# 1-Schematic_UA741.net
KiCad netlist of a schematic drawn in EasyEDA
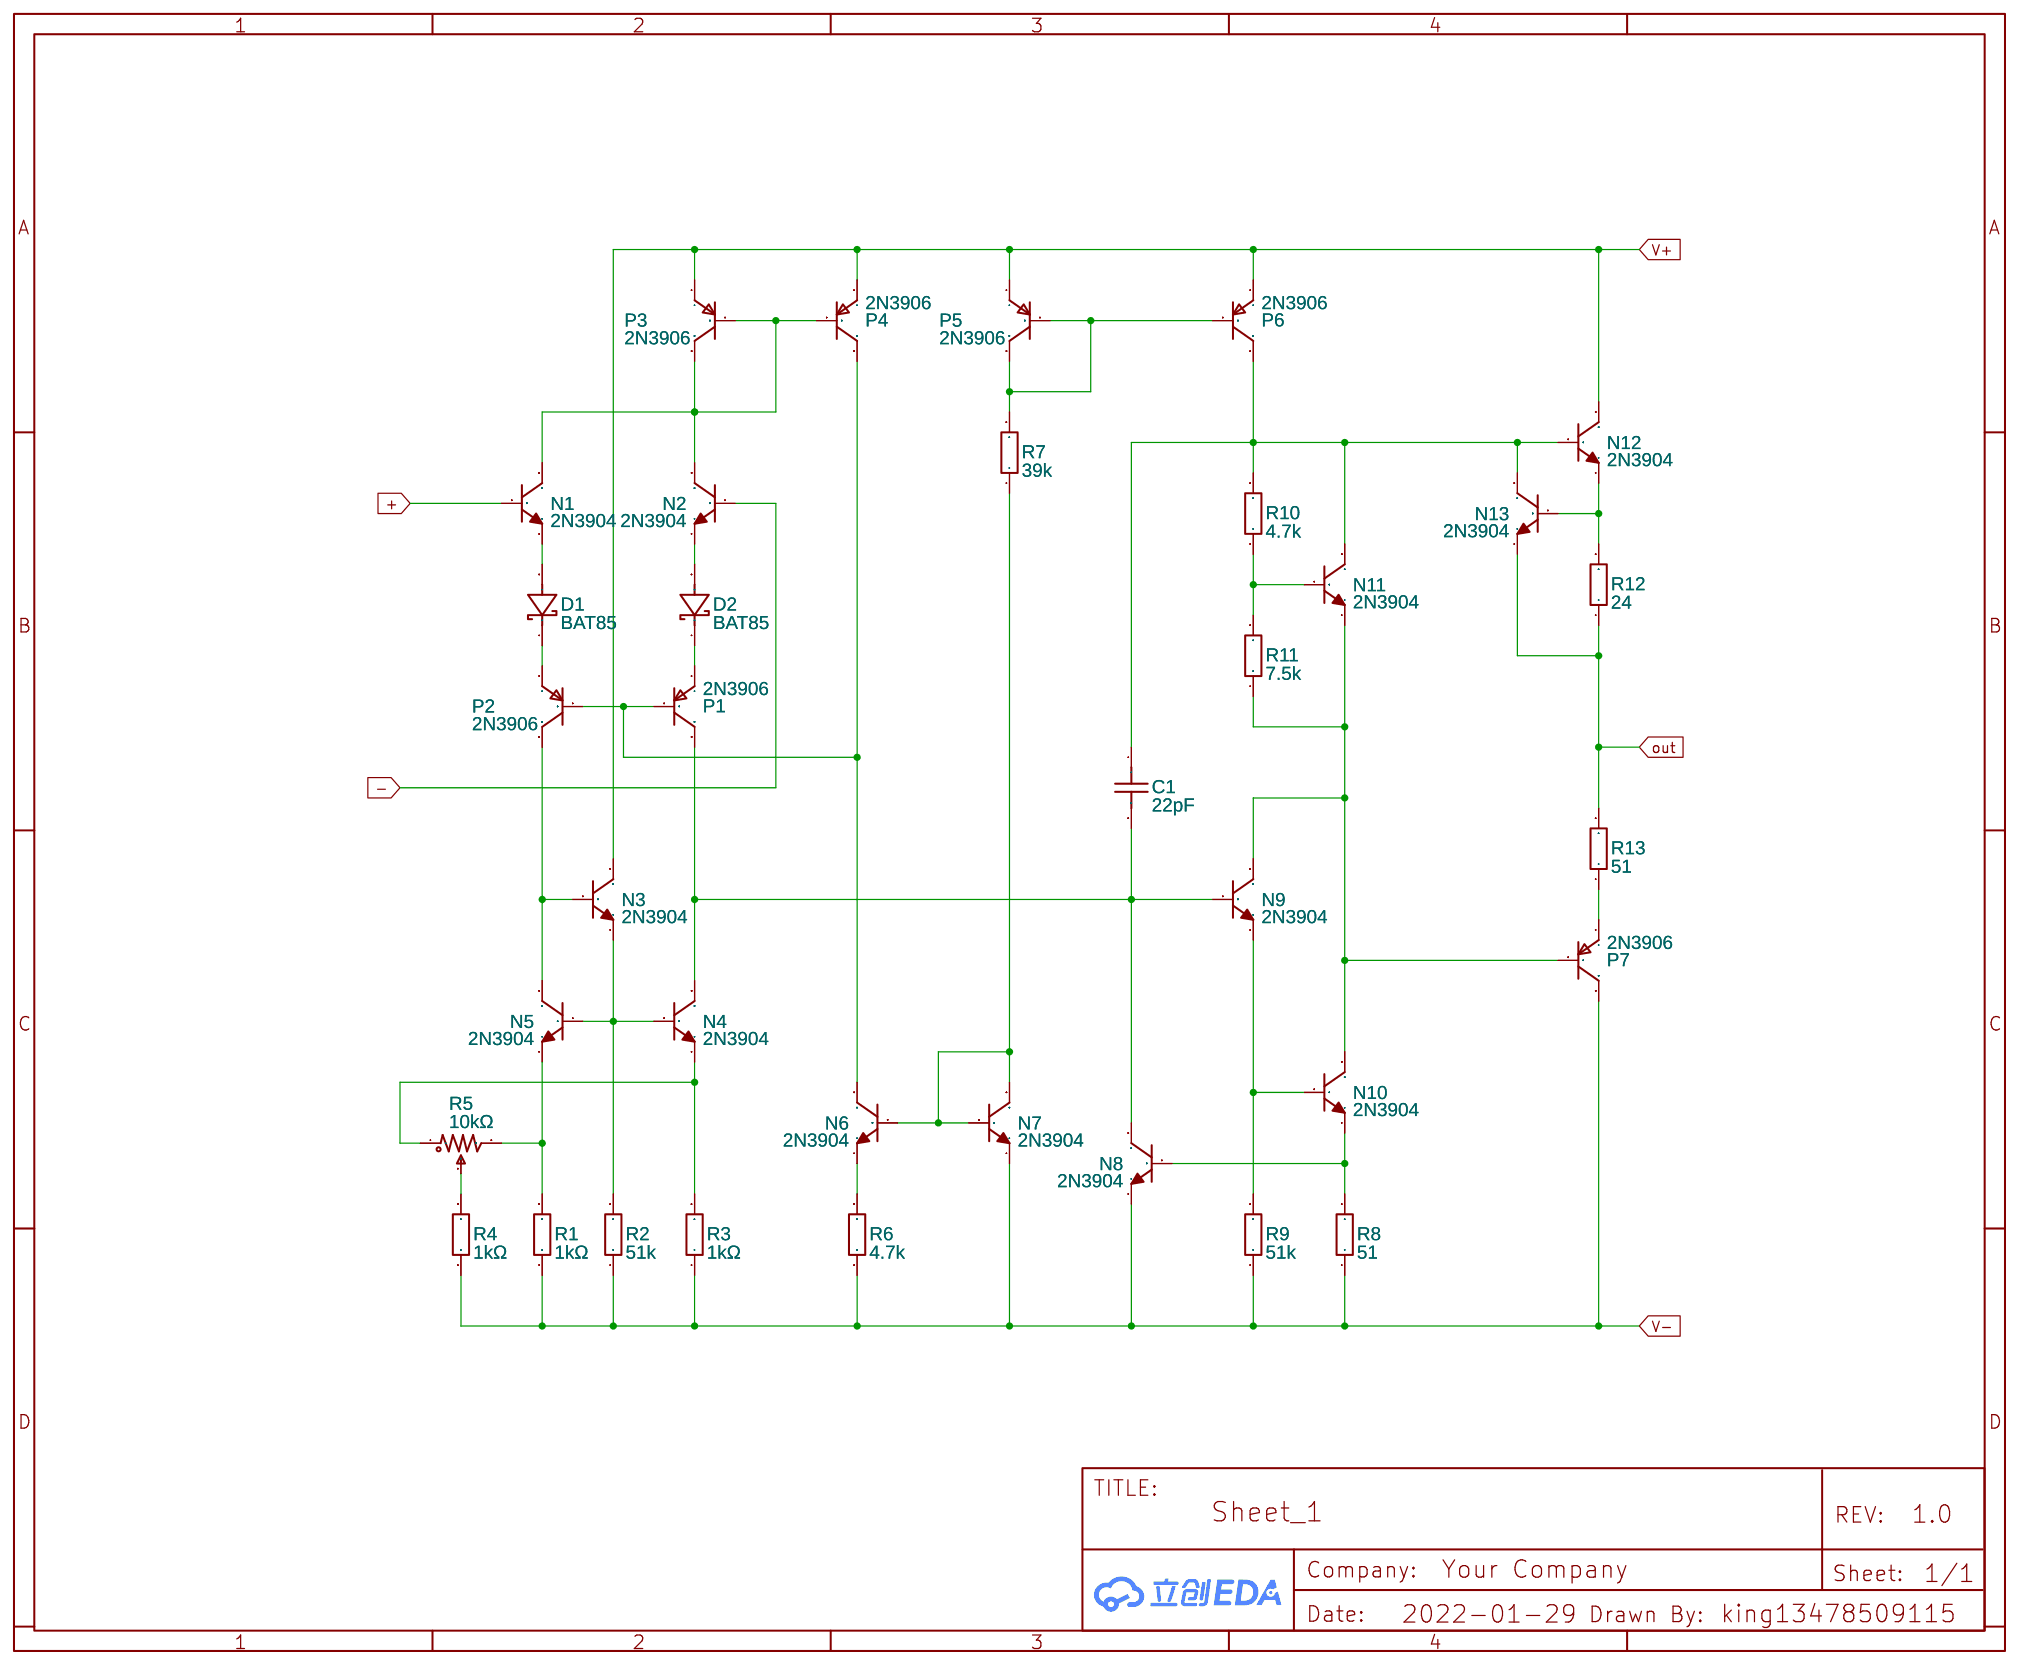
[diagram p0: schematic sheet]

(export (version "E")
  (design (tool "Eeschema 10.0.6"))
  (components
    (comp (ref "C1")
      (value "22pF")
      (fields
        (field (name "BOM_Manufacturer Part") "0805CG220J101NT")
        (field (name "BOM_Supplier Part") "C157623")
      )
      (libsource (lib "") (part "0805CG220J101NT"))
    )
    (comp (ref "D1")
      (value "BAT85")
      (fields (field (name "BOM_Manufacturer Part") "BAT85,113") (field (name "BOM_Supplier Part") "C549292"))
      (libsource (lib "") (part "BAT85,113"))
    )
    (comp (ref "D2")
      (value "BAT85")
      (fields (field (name "BOM_Manufacturer Part") "BAT85,113") (field (name "BOM_Supplier Part") "C549292"))
      (libsource (lib "") (part "BAT85,113"))
    )
    (comp (ref "N1")
      (value "2N3904")
      (fields (field (name "BOM_Supplier Part") "C118538"))
      (libsource (lib "") (part "2N3904"))
    )
    (comp (ref "N2")
      (value "2N3904")
      (fields (field (name "BOM_Supplier Part") "C118538"))
      (libsource (lib "") (part "2N3904_1"))
    )
    (comp (ref "N3")
      (value "2N3904")
      (fields (field (name "BOM_Supplier Part") "C118538"))
      (libsource (lib "") (part "2N3904"))
    )
    (comp (ref "N4")
      (value "2N3904")
      (fields (field (name "BOM_Supplier Part") "C118538"))
      (libsource (lib "") (part "2N3904"))
    )
    (comp (ref "N5")
      (value "2N3904")
      (fields (field (name "BOM_Supplier Part") "C118538"))
      (libsource (lib "") (part "2N3904_1"))
    )
    (comp (ref "N6")
      (value "2N3904")
      (fields (field (name "BOM_Supplier Part") "C118538"))
      (libsource (lib "") (part "2N3904_1"))
    )
    (comp (ref "N7")
      (value "2N3904")
      (fields (field (name "BOM_Supplier Part") "C118538"))
      (libsource (lib "") (part "2N3904"))
    )
    (comp (ref "N8")
      (value "2N3904")
      (fields (field (name "BOM_Supplier Part") "C118538"))
      (libsource (lib "") (part "2N3904_1"))
    )
    (comp (ref "N9")
      (value "2N3904")
      (fields (field (name "BOM_Supplier Part") "C118538"))
      (libsource (lib "") (part "2N3904"))
    )
    (comp (ref "N10")
      (value "2N3904")
      (fields (field (name "BOM_Supplier Part") "C118538"))
      (libsource (lib "") (part "2N3904"))
    )
    (comp (ref "N11")
      (value "2N3904")
      (fields (field (name "BOM_Supplier Part") "C118538"))
      (libsource (lib "") (part "2N3904"))
    )
    (comp (ref "N12")
      (value "2N3904")
      (fields (field (name "BOM_Supplier Part") "C118538"))
      (libsource (lib "") (part "2N3904"))
    )
    (comp (ref "N13")
      (value "2N3904")
      (fields (field (name "BOM_Supplier Part") "C118538"))
      (libsource (lib "") (part "2N3904_1"))
    )
    (comp (ref "P1")
      (value "2N3906")
      (fields (field (name "BOM_Supplier Part") "C713606"))
      (libsource (lib "") (part "2N3906_C713606"))
    )
    (comp (ref "P2")
      (value "2N3906")
      (fields (field (name "BOM_Supplier Part") "C713606"))
      (libsource (lib "") (part "2N3906_C713606_1"))
    )
    (comp (ref "P3")
      (value "2N3906")
      (fields (field (name "BOM_Supplier Part") "C713606"))
      (libsource (lib "") (part "2N3906_C713606_1"))
    )
    (comp (ref "P4")
      (value "2N3906")
      (fields (field (name "BOM_Supplier Part") "C713606"))
      (libsource (lib "") (part "2N3906_C713606"))
    )
    (comp (ref "P5")
      (value "2N3906")
      (fields (field (name "BOM_Supplier Part") "C713606"))
      (libsource (lib "") (part "2N3906_C713606_1"))
    )
    (comp (ref "P6")
      (value "2N3906")
      (fields (field (name "BOM_Supplier Part") "C713606"))
      (libsource (lib "") (part "2N3906_C713606"))
    )
    (comp (ref "P7")
      (value "2N3906")
      (fields (field (name "BOM_Supplier Part") "C713606"))
      (libsource (lib "") (part "2N3906_C713606"))
    )
    (comp (ref "R1")
      (value "1kΩ")
      (fields
        (field (name "BOM_Manufacturer Part") "QR0805F1KP05")
        (field (name "BOM_Supplier Part") "C176197")
      )
      (libsource (lib "") (part "QR0805F1KP05"))
    )
    (comp (ref "R2")
      (value "51k")
      (fields
        (field (name "BOM_Manufacturer Part") "QR0805F1KP05")
        (field (name "BOM_Supplier Part") "C176197")
      )
      (libsource (lib "") (part "QR0805F1KP05"))
    )
    (comp (ref "R3")
      (value "1kΩ")
      (fields
        (field (name "BOM_Manufacturer Part") "QR0805F1KP05")
        (field (name "BOM_Supplier Part") "C176197")
      )
      (libsource (lib "") (part "QR0805F1KP05"))
    )
    (comp (ref "R4")
      (value "1kΩ")
      (fields
        (field (name "BOM_Manufacturer Part") "QR0805F1KP05")
        (field (name "BOM_Supplier Part") "C176197")
      )
      (libsource (lib "") (part "QR0805F1KP05"))
    )
    (comp (ref "R5")
      (value "10kΩ")
      (fields
        (field (name "BOM_Manufacturer Part") "3296W-1-103")
        (field (name "BOM_Supplier Part") "C118954")
      )
      (libsource (lib "") (part "3296W-1-103"))
    )
    (comp (ref "R6")
      (value "4.7k")
      (fields
        (field (name "BOM_Manufacturer Part") "QR0805F1KP05")
        (field (name "BOM_Supplier Part") "C176197")
      )
      (libsource (lib "") (part "QR0805F1KP05"))
    )
    (comp (ref "R7")
      (value "39k")
      (fields
        (field (name "BOM_Manufacturer Part") "QR0805F1KP05")
        (field (name "BOM_Supplier Part") "C176197")
      )
      (libsource (lib "") (part "QR0805F1KP05"))
    )
    (comp (ref "R8")
      (value "51")
      (fields
        (field (name "BOM_Manufacturer Part") "QR0805F1KP05")
        (field (name "BOM_Supplier Part") "C176197")
      )
      (libsource (lib "") (part "QR0805F1KP05"))
    )
    (comp (ref "R9")
      (value "51k")
      (fields
        (field (name "BOM_Manufacturer Part") "QR0805F1KP05")
        (field (name "BOM_Supplier Part") "C176197")
      )
      (libsource (lib "") (part "QR0805F1KP05"))
    )
    (comp (ref "R10")
      (value "4.7k")
      (fields
        (field (name "BOM_Manufacturer Part") "QR0805F1KP05")
        (field (name "BOM_Supplier Part") "C176197")
      )
      (libsource (lib "") (part "QR0805F1KP05"))
    )
    (comp (ref "R11")
      (value "7.5k")
      (fields
        (field (name "BOM_Manufacturer Part") "QR0805F1KP05")
        (field (name "BOM_Supplier Part") "C176197")
      )
      (libsource (lib "") (part "QR0805F1KP05"))
    )
    (comp (ref "R12")
      (value "24")
      (fields
        (field (name "BOM_Manufacturer Part") "QR0805F1KP05")
        (field (name "BOM_Supplier Part") "C176197")
      )
      (libsource (lib "") (part "QR0805F1KP05"))
    )
    (comp (ref "R13")
      (value "51")
      (fields
        (field (name "BOM_Manufacturer Part") "QR0805F1KP05")
        (field (name "BOM_Supplier Part") "C176197")
      )
      (libsource (lib "") (part "QR0805F1KP05"))
    )
  )
  (nets
    (net (code "1") (name "+") (class "Default")
      (node (ref "N1") (pin "2") (pinfunction "B_2") (pintype "unspecified"))
    )
    (net (code "2") (name "-") (class "Default")
      (node (ref "N2") (pin "2") (pinfunction "B_2") (pintype "unspecified"))
    )
    (net (code "3") (name "Net-(D1-A)") (class "Default")
      (node (ref "D1") (pin "2") (pinfunction "A_2") (pintype "unspecified"))
      (node (ref "N1") (pin "1") (pinfunction "E_1") (pintype "unspecified"))
    )
    (net (code "4") (name "Net-(D1-K)") (class "Default")
      (node (ref "D1") (pin "1") (pinfunction "K_1") (pintype "unspecified"))
      (node (ref "P2") (pin "1") (pinfunction "E_1") (pintype "unspecified"))
    )
    (net (code "5") (name "Net-(D2-A)") (class "Default")
      (node (ref "D2") (pin "2") (pinfunction "A_2") (pintype "unspecified"))
      (node (ref "N2") (pin "1") (pinfunction "E_1") (pintype "unspecified"))
    )
    (net (code "6") (name "Net-(D2-K)") (class "Default")
      (node (ref "D2") (pin "1") (pinfunction "K_1") (pintype "unspecified"))
      (node (ref "P1") (pin "1") (pinfunction "E_1") (pintype "unspecified"))
    )
    (net (code "7") (name "Net-(N1-C)") (class "Default")
      (node (ref "N1") (pin "3") (pinfunction "C_3") (pintype "unspecified"))
      (node (ref "N2") (pin "3") (pinfunction "C_3") (pintype "unspecified"))
      (node (ref "P3") (pin "2") (pinfunction "B_2") (pintype "unspecified"))
      (node (ref "P3") (pin "3") (pinfunction "C_3") (pintype "unspecified"))
      (node (ref "P4") (pin "2") (pinfunction "B_2") (pintype "unspecified"))
    )
    (net (code "8") (name "Net-(N3-B)") (class "Default")
      (node (ref "N3") (pin "2") (pinfunction "B_2") (pintype "unspecified"))
      (node (ref "N5") (pin "3") (pinfunction "C_3") (pintype "unspecified"))
      (node (ref "P2") (pin "3") (pinfunction "C_3") (pintype "unspecified"))
    )
    (net (code "9") (name "Net-(N3-E)") (class "Default")
      (node (ref "N3") (pin "1") (pinfunction "E_1") (pintype "unspecified"))
      (node (ref "N4") (pin "2") (pinfunction "B_2") (pintype "unspecified"))
      (node (ref "N5") (pin "2") (pinfunction "B_2") (pintype "unspecified"))
      (node (ref "R2") (pin "2") (pinfunction "2_2") (pintype "unspecified"))
    )
    (net (code "10") (name "Net-(N4-C)") (class "Default")
      (node (ref "C1") (pin "2") (pinfunction "2_2") (pintype "unspecified"))
      (node (ref "N4") (pin "3") (pinfunction "C_3") (pintype "unspecified"))
      (node (ref "N8") (pin "3") (pinfunction "C_3") (pintype "unspecified"))
      (node (ref "N9") (pin "2") (pinfunction "B_2") (pintype "unspecified"))
      (node (ref "P1") (pin "3") (pinfunction "C_3") (pintype "unspecified"))
    )
    (net (code "11") (name "Net-(N4-E)") (class "Default")
      (node (ref "N4") (pin "1") (pinfunction "E_1") (pintype "unspecified"))
      (node (ref "R3") (pin "2") (pinfunction "2_2") (pintype "unspecified"))
      (node (ref "R5") (pin "1") (pinfunction "1_1") (pintype "unspecified"))
    )
    (net (code "12") (name "Net-(N5-E)") (class "Default")
      (node (ref "N5") (pin "1") (pinfunction "E_1") (pintype "unspecified"))
      (node (ref "R1") (pin "2") (pinfunction "2_2") (pintype "unspecified"))
      (node (ref "R5") (pin "3") (pinfunction "3_3") (pintype "unspecified"))
    )
    (net (code "13") (name "Net-(N6-B)") (class "Default")
      (node (ref "N6") (pin "2") (pinfunction "B_2") (pintype "unspecified"))
      (node (ref "N7") (pin "2") (pinfunction "B_2") (pintype "unspecified"))
      (node (ref "N7") (pin "3") (pinfunction "C_3") (pintype "unspecified"))
      (node (ref "R7") (pin "1") (pinfunction "1_1") (pintype "unspecified"))
    )
    (net (code "14") (name "Net-(N6-C)") (class "Default")
      (node (ref "N6") (pin "3") (pinfunction "C_3") (pintype "unspecified"))
      (node (ref "P1") (pin "2") (pinfunction "B_2") (pintype "unspecified"))
      (node (ref "P2") (pin "2") (pinfunction "B_2") (pintype "unspecified"))
      (node (ref "P4") (pin "3") (pinfunction "C_3") (pintype "unspecified"))
    )
    (net (code "15") (name "Net-(N6-E)") (class "Default")
      (node (ref "N6") (pin "1") (pinfunction "E_1") (pintype "unspecified"))
      (node (ref "R6") (pin "2") (pinfunction "2_2") (pintype "unspecified"))
    )
    (net (code "16") (name "Net-(N10-B)") (class "Default")
      (node (ref "N10") (pin "2") (pinfunction "B_2") (pintype "unspecified"))
      (node (ref "N9") (pin "1") (pinfunction "E_1") (pintype "unspecified"))
      (node (ref "R9") (pin "2") (pinfunction "2_2") (pintype "unspecified"))
    )
    (net (code "17") (name "Net-(N10-C)") (class "Default")
      (node (ref "N10") (pin "3") (pinfunction "C_3") (pintype "unspecified"))
      (node (ref "N11") (pin "1") (pinfunction "E_1") (pintype "unspecified"))
      (node (ref "N9") (pin "3") (pinfunction "C_3") (pintype "unspecified"))
      (node (ref "P7") (pin "2") (pinfunction "B_2") (pintype "unspecified"))
      (node (ref "R11") (pin "1") (pinfunction "1_1") (pintype "unspecified"))
    )
    (net (code "18") (name "Net-(N10-E)") (class "Default")
      (node (ref "N10") (pin "1") (pinfunction "E_1") (pintype "unspecified"))
      (node (ref "N8") (pin "2") (pinfunction "B_2") (pintype "unspecified"))
      (node (ref "R8") (pin "2") (pinfunction "2_2") (pintype "unspecified"))
    )
    (net (code "19") (name "Net-(N11-B)") (class "Default")
      (node (ref "N11") (pin "2") (pinfunction "B_2") (pintype "unspecified"))
      (node (ref "R10") (pin "1") (pinfunction "1_1") (pintype "unspecified"))
      (node (ref "R11") (pin "2") (pinfunction "2_2") (pintype "unspecified"))
    )
    (net (code "20") (name "Net-(N11-C)") (class "Default")
      (node (ref "C1") (pin "1") (pinfunction "1_1") (pintype "unspecified"))
      (node (ref "N11") (pin "3") (pinfunction "C_3") (pintype "unspecified"))
      (node (ref "N12") (pin "2") (pinfunction "B_2") (pintype "unspecified"))
      (node (ref "N13") (pin "3") (pinfunction "C_3") (pintype "unspecified"))
      (node (ref "P6") (pin "3") (pinfunction "C_3") (pintype "unspecified"))
      (node (ref "R10") (pin "2") (pinfunction "2_2") (pintype "unspecified"))
    )
    (net (code "21") (name "Net-(N12-E)") (class "Default")
      (node (ref "N12") (pin "1") (pinfunction "E_1") (pintype "unspecified"))
      (node (ref "N13") (pin "2") (pinfunction "B_2") (pintype "unspecified"))
      (node (ref "R12") (pin "2") (pinfunction "2_2") (pintype "unspecified"))
    )
    (net (code "22") (name "Net-(P5-B)") (class "Default")
      (node (ref "P5") (pin "2") (pinfunction "B_2") (pintype "unspecified"))
      (node (ref "P5") (pin "3") (pinfunction "C_3") (pintype "unspecified"))
      (node (ref "P6") (pin "2") (pinfunction "B_2") (pintype "unspecified"))
      (node (ref "R7") (pin "2") (pinfunction "2_2") (pintype "unspecified"))
    )
    (net (code "23") (name "Net-(P7-E)") (class "Default")
      (node (ref "P7") (pin "1") (pinfunction "E_1") (pintype "unspecified"))
      (node (ref "R13") (pin "1") (pinfunction "1_1") (pintype "unspecified"))
    )
    (net (code "24") (name "Net-(R4-Pad2)") (class "Default")
      (node (ref "R4") (pin "2") (pinfunction "2_2") (pintype "unspecified"))
      (node (ref "R5") (pin "2") (pinfunction "2_2") (pintype "unspecified"))
    )
    (net (code "25") (name "V+") (class "Default")
      (node (ref "N12") (pin "3") (pinfunction "C_3") (pintype "unspecified"))
      (node (ref "N3") (pin "3") (pinfunction "C_3") (pintype "unspecified"))
      (node (ref "P3") (pin "1") (pinfunction "E_1") (pintype "unspecified"))
      (node (ref "P4") (pin "1") (pinfunction "E_1") (pintype "unspecified"))
      (node (ref "P5") (pin "1") (pinfunction "E_1") (pintype "unspecified"))
      (node (ref "P6") (pin "1") (pinfunction "E_1") (pintype "unspecified"))
    )
    (net (code "26") (name "V-") (class "Default")
      (node (ref "N7") (pin "1") (pinfunction "E_1") (pintype "unspecified"))
      (node (ref "N8") (pin "1") (pinfunction "E_1") (pintype "unspecified"))
      (node (ref "P7") (pin "3") (pinfunction "C_3") (pintype "unspecified"))
      (node (ref "R1") (pin "1") (pinfunction "1_1") (pintype "unspecified"))
      (node (ref "R2") (pin "1") (pinfunction "1_1") (pintype "unspecified"))
      (node (ref "R3") (pin "1") (pinfunction "1_1") (pintype "unspecified"))
      (node (ref "R4") (pin "1") (pinfunction "1_1") (pintype "unspecified"))
      (node (ref "R6") (pin "1") (pinfunction "1_1") (pintype "unspecified"))
      (node (ref "R8") (pin "1") (pinfunction "1_1") (pintype "unspecified"))
      (node (ref "R9") (pin "1") (pinfunction "1_1") (pintype "unspecified"))
    )
    (net (code "27") (name "out") (class "Default")
      (node (ref "N13") (pin "1") (pinfunction "E_1") (pintype "unspecified"))
      (node (ref "R12") (pin "1") (pinfunction "1_1") (pintype "unspecified"))
      (node (ref "R13") (pin "2") (pinfunction "2_2") (pintype "unspecified"))
    )
  )
)
